# bicyclelab-manager-v3_1.net
KiCad netlist of a schematic drawn in EAGLE
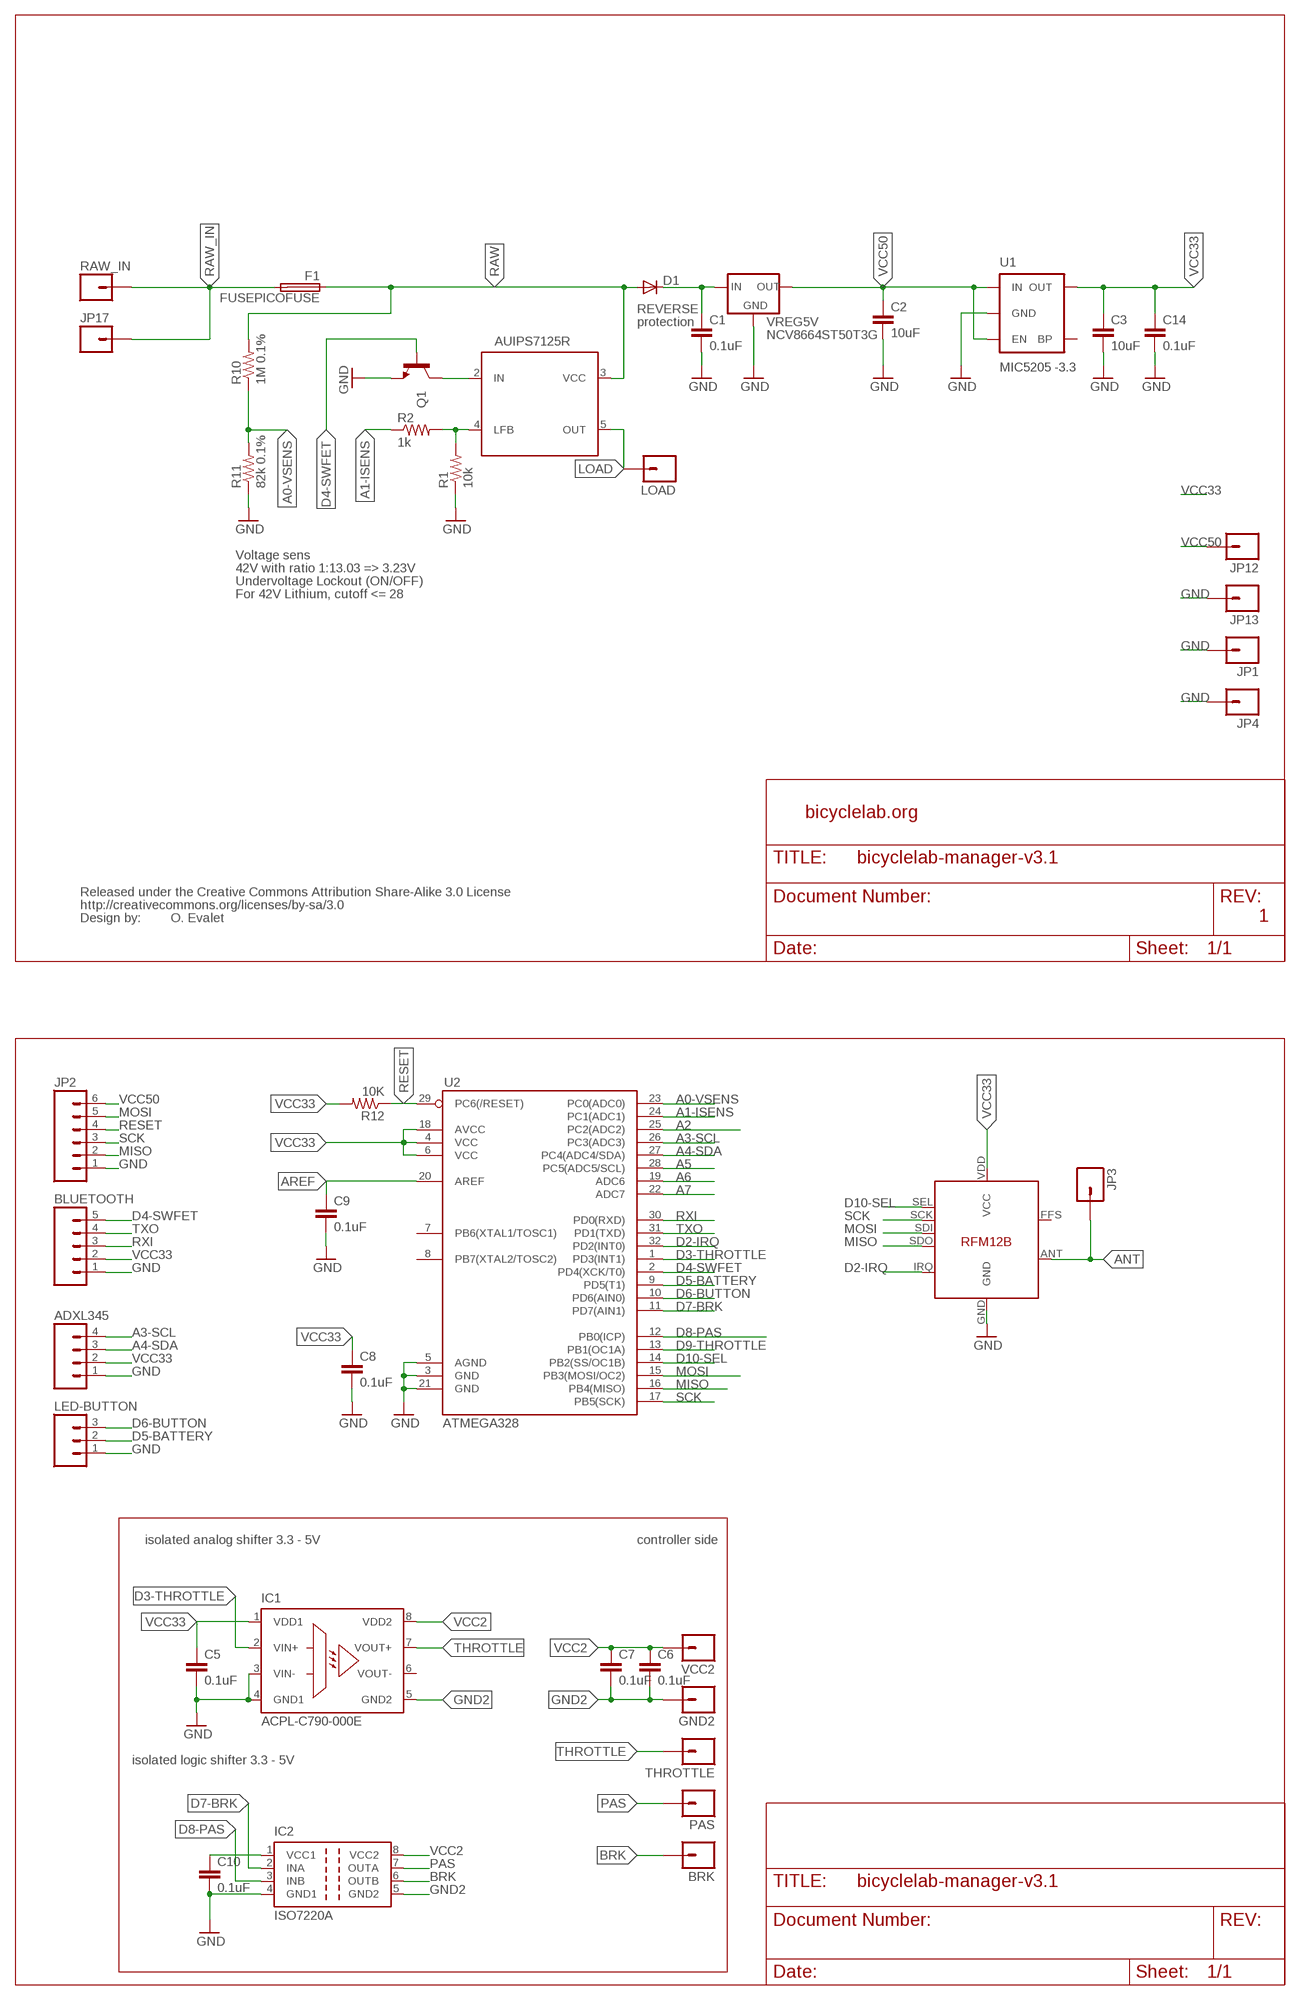
[diagram p0: schematic, sheet 1]

(export (version "E")
  (design (tool "Eeschema 10.0.6"))
  (components
    (comp (ref "ADXL345")
      (value "M04PTH")
      (footprint "eagle-import:1X04")
      (libsource (lib "eagle-import") (part "M04PTH"))
    )
    (comp (ref "BLUETOOTH")
      (value "M05PTH")
      (footprint "eagle-import:1X05")
      (libsource (lib "eagle-import") (part "M05PTH"))
    )
    (comp (ref "BRK")
      (value "M01PTH")
      (footprint "eagle-import:1X01")
      (libsource (lib "eagle-import") (part "SparkFun_M01PTH"))
    )
    (comp (ref "C1")
      (value "0.1uF")
      (footprint "eagle-import:0805")
      (libsource (lib "eagle-import") (part "CAP0805"))
    )
    (comp (ref "C2")
      (value "10uF")
      (footprint "eagle-import:0805")
      (libsource (lib "eagle-import") (part "CAP0805"))
    )
    (comp (ref "C3")
      (value "10uF")
      (footprint "eagle-import:0805")
      (libsource (lib "eagle-import") (part "CAP0805"))
    )
    (comp (ref "C5")
      (value "0.1uF")
      (footprint "eagle-import:0805")
      (libsource (lib "eagle-import") (part "CAP0805"))
    )
    (comp (ref "C6")
      (value "0.1uF")
      (footprint "eagle-import:0805")
      (libsource (lib "eagle-import") (part "CAP0805"))
    )
    (comp (ref "C7")
      (value "0.1uF")
      (footprint "eagle-import:0805")
      (libsource (lib "eagle-import") (part "CAP0805"))
    )
    (comp (ref "C8")
      (value "0.1uF")
      (footprint "eagle-import:0603-CAP")
      (libsource (lib "eagle-import") (part "CAP0603-CAP"))
    )
    (comp (ref "C9")
      (value "0.1uF")
      (footprint "eagle-import:0603-CAP")
      (libsource (lib "eagle-import") (part "CAP0603-CAP"))
    )
    (comp (ref "C10")
      (value "0.1uF")
      (footprint "eagle-import:0805")
      (libsource (lib "eagle-import") (part "CAP0805"))
    )
    (comp (ref "C14")
      (value "0.1uF")
      (footprint "eagle-import:0603-CAP")
      (libsource (lib "eagle-import") (part "CAP0603-CAP"))
    )
    (comp (ref "D1")
      (value "DIODESOD")
      (footprint "eagle-import:SOD-323")
      (libsource (lib "eagle-import") (part "DIODESOD"))
    )
    (comp (ref "F1")
      (value "FUSEPICOFUSE")
      (footprint "eagle-import:PICOFUSE")
      (libsource (lib "eagle-import") (part "FUSEPICOFUSE"))
    )
    (comp (ref "GND2")
      (value "M01PTH")
      (footprint "eagle-import:1X01")
      (libsource (lib "eagle-import") (part "SparkFun_M01PTH"))
    )
    (comp (ref "IC1")
      (value "ACPL-C790-000E")
      (footprint "eagle-import:SSO8")
      (libsource (lib "eagle-import") (part "ACPL-790SSO8"))
    )
    (comp (ref "IC2")
      (value "ISO7220A")
      (footprint "eagle-import:SO-08")
      (fields (field (name "MPN") "ISO7220AD"))
      (libsource (lib "eagle-import") (part "ISO7220A"))
    )
    (comp (ref "JP1")
      (value "M01PTH_2MM")
      (footprint "eagle-import:1X01_2MM")
      (libsource (lib "eagle-import") (part "SparkFun_M01PTH_2MM"))
    )
    (comp (ref "JP2")
      (value "M06EM406")
      (footprint "eagle-import:EM406")
      (libsource (lib "eagle-import") (part "M06EM406"))
    )
    (comp (ref "JP3")
      (value "M01SMD-4.5X1.5")
      (footprint "eagle-import:PAD-1.5X4.5")
      (libsource (lib "eagle-import") (part "M01SMD-4.5X1.5"))
    )
    (comp (ref "JP4")
      (value "M01PTH_2MM")
      (footprint "eagle-import:1X01_2MM")
      (libsource (lib "eagle-import") (part "SparkFun_M01PTH_2MM"))
    )
    (comp (ref "JP12")
      (value "M01PTH")
      (footprint "eagle-import:1X01")
      (libsource (lib "eagle-import") (part "SparkFun_M01PTH"))
    )
    (comp (ref "JP13")
      (value "M01PTH")
      (footprint "eagle-import:1X01")
      (libsource (lib "eagle-import") (part "SparkFun_M01PTH"))
    )
    (comp (ref "JP17")
      (value "M01PTH_2MM")
      (footprint "eagle-import:1X01_2MM")
      (libsource (lib "eagle-import") (part "SparkFun_M01PTH_2MM"))
    )
    (comp (ref "LED-BUTTON")
      (value "M03PTH")
      (footprint "eagle-import:1X03")
      (libsource (lib "eagle-import") (part "M03PTH"))
    )
    (comp (ref "LOAD")
      (value "M01PTH_2MM")
      (footprint "eagle-import:1X01_2MM")
      (libsource (lib "eagle-import") (part "SparkFun_M01PTH_2MM"))
    )
    (comp (ref "PAS")
      (value "M01PTH")
      (footprint "eagle-import:1X01")
      (libsource (lib "eagle-import") (part "SparkFun_M01PTH"))
    )
    (comp (ref "Q1")
      (value "TRANSISTOR_NPNSOT23-3")
      (footprint "eagle-import:SOT23-3")
      (libsource (lib "eagle-import") (part "TRANSISTOR_NPNSOT23-3"))
    )
    (comp (ref "R1")
      (value "10k")
      (footprint "eagle-import:0805")
      (libsource (lib "eagle-import") (part "RESISTOR"))
    )
    (comp (ref "R2")
      (value "1k")
      (footprint "eagle-import:0805")
      (libsource (lib "eagle-import") (part "RESISTOR"))
    )
    (comp (ref "R10")
      (value "1M 0.1%")
      (footprint "eagle-import:0805")
      (libsource (lib "eagle-import") (part "RESISTOR"))
    )
    (comp (ref "R11")
      (value "82k 0.1%")
      (footprint "eagle-import:0805")
      (libsource (lib "eagle-import") (part "RESISTOR"))
    )
    (comp (ref "R12")
      (value "10K")
      (footprint "eagle-import:0603-RES")
      (libsource (lib "eagle-import") (part "RESISTOR0603-RES"))
    )
    (comp (ref "RAW_IN")
      (value "M01PTH_2MM")
      (footprint "eagle-import:1X01_2MM")
      (libsource (lib "eagle-import") (part "SparkFun_M01PTH_2MM"))
    )
    (comp (ref "THROTTLE")
      (value "M01PTH")
      (footprint "eagle-import:1X01")
      (libsource (lib "eagle-import") (part "SparkFun_M01PTH"))
    )
    (comp (ref "U$1")
      (value "RFM12B")
      (footprint "eagle-import:RFM12B")
      (libsource (lib "eagle-import") (part "RFM12B"))
    )
    (comp (ref "U$5")
      (value "CREATIVE_COMMONS")
      (footprint "eagle-import:CREATIVE_COMMONS")
      (libsource (lib "eagle-import") (part "CREATIVE_COMMONS"))
    )
    (comp (ref "U$8")
      (value "AUIPS7125R")
      (footprint "eagle-import:DPAK-5")
      (libsource (lib "eagle-import") (part "AUIPS7125R"))
    )
    (comp (ref "U1")
      (value "MIC5205 -3.3")
      (footprint "eagle-import:SOT23-5")
      (libsource (lib "eagle-import") (part "V_REG_LDOSMD"))
    )
    (comp (ref "U2")
      (value "ATMEGA328")
      (footprint "eagle-import:TQFP32-08")
      (libsource (lib "eagle-import") (part "ATMEGA168"))
    )
    (comp (ref "VCC2")
      (value "M01PTH")
      (footprint "eagle-import:1X01")
      (libsource (lib "eagle-import") (part "SparkFun_M01PTH"))
    )
    (comp (ref "VREG5V")
      (value "NCV8664ST50T3G")
      (footprint "eagle-import:SOT223")
      (libsource (lib "eagle-import") (part "V_REG_MIC2920"))
    )
  )
  (nets
    (net (code "1") (name "/A2") (class "Default")
      (node (ref "U2") (pin "25") (pinfunction "PC2(ADC2)_25") (pintype "bidirectional"))
    )
    (net (code "2") (name "/A3-SCL") (class "Default")
      (node (ref "ADXL345") (pin "4") (pinfunction "4_4") (pintype "passive"))
      (node (ref "U2") (pin "26") (pinfunction "PC3(ADC3)_26") (pintype "bidirectional"))
    )
    (net (code "3") (name "/A4-SDA") (class "Default")
      (node (ref "ADXL345") (pin "3") (pinfunction "3_3") (pintype "passive"))
      (node (ref "U2") (pin "27") (pinfunction "PC4(ADC4/SDA)_27") (pintype "bidirectional"))
    )
    (net (code "4") (name "/A5") (class "Default")
      (node (ref "U2") (pin "28") (pinfunction "PC5(ADC5/SCL)_28") (pintype "bidirectional"))
    )
    (net (code "5") (name "/A6") (class "Default")
      (node (ref "U2") (pin "19") (pinfunction "ADC6_19") (pintype "bidirectional"))
    )
    (net (code "6") (name "/A7") (class "Default")
      (node (ref "U2") (pin "22") (pinfunction "ADC7_22") (pintype "bidirectional"))
    )
    (net (code "7") (name "/D2-IRQ") (class "Default")
      (node (ref "U$1") (pin "IRQ") (pinfunction "IRQ_IRQ") (pintype "open_collector"))
      (node (ref "U2") (pin "32") (pinfunction "PD2(INT0)_32") (pintype "bidirectional"))
    )
    (net (code "8") (name "/D5-BATTERY") (class "Default")
      (node (ref "LED-BUTTON") (pin "2") (pinfunction "2_2") (pintype "passive"))
      (node (ref "U2") (pin "9") (pinfunction "PD5(T1)_9") (pintype "bidirectional"))
    )
    (net (code "9") (name "/D6-BUTTON") (class "Default")
      (node (ref "LED-BUTTON") (pin "3") (pinfunction "3_3") (pintype "passive"))
      (node (ref "U2") (pin "10") (pinfunction "PD6(AIN0)_10") (pintype "bidirectional"))
    )
    (net (code "10") (name "/D9-THROTTLE") (class "Default")
      (node (ref "U2") (pin "13") (pinfunction "PB1(OC1A)_13") (pintype "bidirectional"))
    )
    (net (code "11") (name "/D10-SEL") (class "Default")
      (node (ref "U$1") (pin "SEL") (pinfunction "SEL_SEL") (pintype "input"))
      (node (ref "U2") (pin "14") (pinfunction "PB2(SS/OC1B)_14") (pintype "bidirectional"))
    )
    (net (code "12") (name "/MISO") (class "Default")
      (node (ref "JP2") (pin "2") (pinfunction "2_2") (pintype "passive"))
      (node (ref "U$1") (pin "SDO") (pinfunction "SDO_SDO") (pintype "output"))
      (node (ref "U2") (pin "16") (pinfunction "PB4(MISO)_16") (pintype "bidirectional"))
    )
    (net (code "13") (name "/MOSI") (class "Default")
      (node (ref "JP2") (pin "5") (pinfunction "5_5") (pintype "passive"))
      (node (ref "U$1") (pin "SDI") (pinfunction "SDI_SDI") (pintype "input"))
      (node (ref "U2") (pin "15") (pinfunction "PB3(MOSI/OC2)_15") (pintype "bidirectional"))
    )
    (net (code "14") (name "/RXI") (class "Default")
      (node (ref "BLUETOOTH") (pin "3") (pinfunction "3_3") (pintype "passive"))
      (node (ref "U2") (pin "30") (pinfunction "PD0(RXD)_30") (pintype "bidirectional"))
    )
    (net (code "15") (name "/SCK") (class "Default")
      (node (ref "JP2") (pin "3") (pinfunction "3_3") (pintype "passive"))
      (node (ref "U$1") (pin "SCK") (pinfunction "SCK_SCK") (pintype "input"))
      (node (ref "U2") (pin "17") (pinfunction "PB5(SCK)_17") (pintype "bidirectional"))
    )
    (net (code "16") (name "/TXO") (class "Default")
      (node (ref "BLUETOOTH") (pin "4") (pinfunction "4_4") (pintype "passive"))
      (node (ref "U2") (pin "31") (pinfunction "PD1(TXD)_31") (pintype "bidirectional"))
    )
    (net (code "17") (name "/VOUT-") (class "Default")
      (node (ref "IC1") (pin "6") (pinfunction "VOUT-_6") (pintype "power_in"))
    )
    (net (code "18") (name "A0-VSENS") (class "Default")
      (node (ref "R10") (pin "1") (pinfunction "1_1") (pintype "passive"))
      (node (ref "R11") (pin "2") (pinfunction "2_2") (pintype "passive"))
      (node (ref "U2") (pin "23") (pinfunction "PC0(ADC0)_23") (pintype "bidirectional"))
    )
    (net (code "19") (name "A1-ISENS") (class "Default")
      (node (ref "R1") (pin "2") (pinfunction "2_2") (pintype "passive"))
      (node (ref "R2") (pin "1") (pinfunction "1_1") (pintype "passive"))
      (node (ref "R2") (pin "2") (pinfunction "2_2") (pintype "passive"))
      (node (ref "U$8") (pin "4") (pinfunction "LFB_4") (pintype "output"))
      (node (ref "U2") (pin "24") (pinfunction "PC1(ADC1)_24") (pintype "bidirectional"))
    )
    (net (code "20") (name "ANT") (class "Default")
      (node (ref "JP3") (pin "P$1") (pinfunction "1_P$1") (pintype "passive"))
      (node (ref "U$1") (pin "ANT") (pinfunction "ANT_ANT") (pintype "passive"))
    )
    (net (code "21") (name "AREF") (class "Default")
      (node (ref "C9") (pin "1") (pinfunction "1_1") (pintype "passive"))
      (node (ref "U2") (pin "20") (pinfunction "AREF_20") (pintype "bidirectional"))
    )
    (net (code "22") (name "BRK") (class "Default")
      (node (ref "BRK") (pin "1") (pinfunction "1_1") (pintype "passive"))
      (node (ref "IC2") (pin "6") (pinfunction "OUTB_6") (pintype "output"))
    )
    (net (code "23") (name "D3-THROTTLE") (class "Default")
      (node (ref "IC1") (pin "2") (pinfunction "VIN+_2") (pintype "power_in"))
      (node (ref "U2") (pin "1") (pinfunction "PD3(INT1)_1") (pintype "bidirectional"))
    )
    (net (code "24") (name "D4-SWFET") (class "Default")
      (node (ref "BLUETOOTH") (pin "5") (pinfunction "5_5") (pintype "passive"))
      (node (ref "Q1") (pin "1") (pinfunction "B_1") (pintype "passive"))
      (node (ref "U2") (pin "2") (pinfunction "PD4(XCK/T0)_2") (pintype "bidirectional"))
    )
    (net (code "25") (name "D7-BRK") (class "Default")
      (node (ref "IC2") (pin "2") (pinfunction "INA_2") (pintype "input"))
      (node (ref "U2") (pin "11") (pinfunction "PD7(AIN1)_11") (pintype "bidirectional"))
    )
    (net (code "26") (name "D8-PAS") (class "Default")
      (node (ref "IC2") (pin "3") (pinfunction "INB_3") (pintype "input"))
      (node (ref "U2") (pin "12") (pinfunction "PB0(ICP)_12") (pintype "bidirectional"))
    )
    (net (code "27") (name "GND") (class "Default")
      (node (ref "ADXL345") (pin "1") (pinfunction "1_1") (pintype "passive"))
      (node (ref "BLUETOOTH") (pin "1") (pinfunction "1_1") (pintype "passive"))
      (node (ref "C1") (pin "2") (pinfunction "2_2") (pintype "passive"))
      (node (ref "C10") (pin "2") (pinfunction "2_2") (pintype "passive"))
      (node (ref "C14") (pin "2") (pinfunction "2_2") (pintype "passive"))
      (node (ref "C2") (pin "2") (pinfunction "2_2") (pintype "passive"))
      (node (ref "C3") (pin "2") (pinfunction "2_2") (pintype "passive"))
      (node (ref "C5") (pin "2") (pinfunction "2_2") (pintype "passive"))
      (node (ref "C8") (pin "2") (pinfunction "2_2") (pintype "passive"))
      (node (ref "C9") (pin "2") (pinfunction "2_2") (pintype "passive"))
      (node (ref "IC1") (pin "3") (pinfunction "VIN-_3") (pintype "power_in"))
      (node (ref "IC1") (pin "4") (pinfunction "GND1_4") (pintype "power_in"))
      (node (ref "IC2") (pin "4") (pinfunction "GND1_4") (pintype "power_in"))
      (node (ref "JP1") (pin "1") (pinfunction "1_1") (pintype "passive"))
      (node (ref "JP13") (pin "1") (pinfunction "1_1") (pintype "passive"))
      (node (ref "JP2") (pin "1") (pinfunction "1_1") (pintype "passive"))
      (node (ref "JP4") (pin "1") (pinfunction "1_1") (pintype "passive"))
      (node (ref "LED-BUTTON") (pin "1") (pinfunction "1_1") (pintype "passive"))
      (node (ref "Q1") (pin "2") (pinfunction "E_2") (pintype "passive"))
      (node (ref "R1") (pin "1") (pinfunction "1_1") (pintype "passive"))
      (node (ref "R11") (pin "1") (pinfunction "1_1") (pintype "passive"))
      (node (ref "U$1") (pin "GND") (pinfunction "GND_GND") (pintype "power_in"))
      (node (ref "U1") (pin "2") (pinfunction "GND_2") (pintype "input"))
      (node (ref "U2") (pin "21") (pinfunction "GND_21") (pintype "bidirectional"))
      (node (ref "U2") (pin "3") (pinfunction "GND_3") (pintype "bidirectional"))
      (node (ref "U2") (pin "5") (pinfunction "AGND_5") (pintype "bidirectional"))
      (node (ref "VREG5V") (pin "2") (pinfunction "GND_2") (pintype "input"))
    )
    (net (code "28") (name "GND2") (class "Default")
      (node (ref "C6") (pin "2") (pinfunction "2_2") (pintype "passive"))
      (node (ref "C7") (pin "2") (pinfunction "2_2") (pintype "passive"))
      (node (ref "GND2") (pin "1") (pinfunction "1_1") (pintype "passive"))
      (node (ref "IC1") (pin "5") (pinfunction "GND2_5") (pintype "power_in"))
      (node (ref "IC2") (pin "5") (pinfunction "GND2_5") (pintype "power_in"))
    )
    (net (code "29") (name "LOAD") (class "Default")
      (node (ref "LOAD") (pin "1") (pinfunction "1_1") (pintype "passive"))
      (node (ref "U$8") (pin "5") (pinfunction "OUT_5") (pintype "output"))
    )
    (net (code "30") (name "Net-(D1-C)") (class "Default")
      (node (ref "C1") (pin "1") (pinfunction "1_1") (pintype "passive"))
      (node (ref "D1") (pin "1") (pinfunction "C_1") (pintype "passive"))
      (node (ref "VREG5V") (pin "1") (pinfunction "IN_1") (pintype "input"))
    )
    (net (code "31") (name "Net-(Q1-C)") (class "Default")
      (node (ref "Q1") (pin "3") (pinfunction "C_3") (pintype "passive"))
      (node (ref "U$8") (pin "2") (pinfunction "IN_2") (pintype "input"))
    )
    (net (code "32") (name "PAS") (class "Default")
      (node (ref "IC2") (pin "7") (pinfunction "OUTA_7") (pintype "output"))
      (node (ref "PAS") (pin "1") (pinfunction "1_1") (pintype "passive"))
    )
    (net (code "33") (name "RAW") (class "Default")
      (node (ref "D1") (pin "2") (pinfunction "A_2") (pintype "passive"))
      (node (ref "F1") (pin "1") (pinfunction "1_1") (pintype "passive"))
      (node (ref "R10") (pin "2") (pinfunction "2_2") (pintype "passive"))
      (node (ref "U$8") (pin "3") (pinfunction "VCC_3") (pintype "input"))
    )
    (net (code "34") (name "RAW_IN") (class "Default")
      (node (ref "F1") (pin "2") (pinfunction "2_2") (pintype "passive"))
      (node (ref "JP17") (pin "1") (pinfunction "1_1") (pintype "passive"))
      (node (ref "RAW_IN") (pin "1") (pinfunction "1_1") (pintype "passive"))
    )
    (net (code "35") (name "RESET") (class "Default")
      (node (ref "JP2") (pin "4") (pinfunction "4_4") (pintype "passive"))
      (node (ref "R12") (pin "1") (pinfunction "1_1") (pintype "passive"))
      (node (ref "U2") (pin "29") (pinfunction "PC6(/RESET)_29") (pintype "bidirectional"))
    )
    (net (code "36") (name "THROTTLE") (class "Default")
      (node (ref "IC1") (pin "7") (pinfunction "VOUT+_7") (pintype "power_in"))
      (node (ref "THROTTLE") (pin "1") (pinfunction "1_1") (pintype "passive"))
    )
    (net (code "37") (name "VCC2") (class "Default")
      (node (ref "C6") (pin "1") (pinfunction "1_1") (pintype "passive"))
      (node (ref "C7") (pin "1") (pinfunction "1_1") (pintype "passive"))
      (node (ref "IC1") (pin "8") (pinfunction "VDD2_8") (pintype "power_in"))
      (node (ref "IC2") (pin "8") (pinfunction "VCC2_8") (pintype "power_in"))
      (node (ref "VCC2") (pin "1") (pinfunction "1_1") (pintype "passive"))
    )
    (net (code "38") (name "VCC33") (class "Default")
      (node (ref "ADXL345") (pin "2") (pinfunction "2_2") (pintype "passive"))
      (node (ref "BLUETOOTH") (pin "2") (pinfunction "2_2") (pintype "passive"))
      (node (ref "C10") (pin "1") (pinfunction "1_1") (pintype "passive"))
      (node (ref "C14") (pin "1") (pinfunction "1_1") (pintype "passive"))
      (node (ref "C3") (pin "1") (pinfunction "1_1") (pintype "passive"))
      (node (ref "C5") (pin "1") (pinfunction "1_1") (pintype "passive"))
      (node (ref "C8") (pin "1") (pinfunction "1_1") (pintype "passive"))
      (node (ref "IC1") (pin "1") (pinfunction "VDD1_1") (pintype "power_in"))
      (node (ref "IC2") (pin "1") (pinfunction "VCC1_1") (pintype "power_in"))
      (node (ref "R12") (pin "2") (pinfunction "2_2") (pintype "passive"))
      (node (ref "U$1") (pin "VDD") (pinfunction "VCC_VDD") (pintype "power_in"))
      (node (ref "U1") (pin "5") (pinfunction "OUT_5") (pintype "passive"))
      (node (ref "U2") (pin "18") (pinfunction "AVCC_18") (pintype "bidirectional"))
      (node (ref "U2") (pin "4") (pinfunction "VCC_4") (pintype "bidirectional"))
      (node (ref "U2") (pin "6") (pinfunction "VCC_6") (pintype "bidirectional"))
    )
    (net (code "39") (name "VCC50") (class "Default")
      (node (ref "C2") (pin "1") (pinfunction "1_1") (pintype "passive"))
      (node (ref "JP12") (pin "1") (pinfunction "1_1") (pintype "passive"))
      (node (ref "JP2") (pin "6") (pinfunction "6_6") (pintype "passive"))
      (node (ref "U1") (pin "1") (pinfunction "IN_1") (pintype "input"))
      (node (ref "U1") (pin "3") (pinfunction "EN_3") (pintype "input"))
      (node (ref "VREG5V") (pin "3") (pinfunction "OUT_3") (pintype "output"))
    )
    (net (code "40") (name "unconnected-(U$1-PadFFS)") (class "Default")
      (node (ref "U$1") (pin "FFS") (pinfunction "FFS_FFS") (pintype "bidirectional"))
    )
    (net (code "41") (name "unconnected-(U$8-NC-Pad1)") (class "Default")
      (node (ref "U$8") (pin "1") (pinfunction "NC_1") (pintype "no_connect"))
    )
    (net (code "42") (name "unconnected-(U1-BP-Pad4)") (class "Default")
      (node (ref "U1") (pin "4") (pinfunction "BP_4") (pintype "input"))
    )
    (net (code "43") (name "unconnected-(U2-PB6(XTAL1{slash}TOSC1)-Pad7)") (class "Default")
      (node (ref "U2") (pin "7") (pinfunction "PB6(XTAL1/TOSC1)_7") (pintype "bidirectional"))
    )
    (net (code "44") (name "unconnected-(U2-PB7(XTAL2{slash}TOSC2)-Pad8)") (class "Default")
      (node (ref "U2") (pin "8") (pinfunction "PB7(XTAL2/TOSC2)_8") (pintype "bidirectional"))
    )
  )
)
